# VoltageRegulator3_3V.net
KiCad netlist of a schematic drawn in Altium Designer
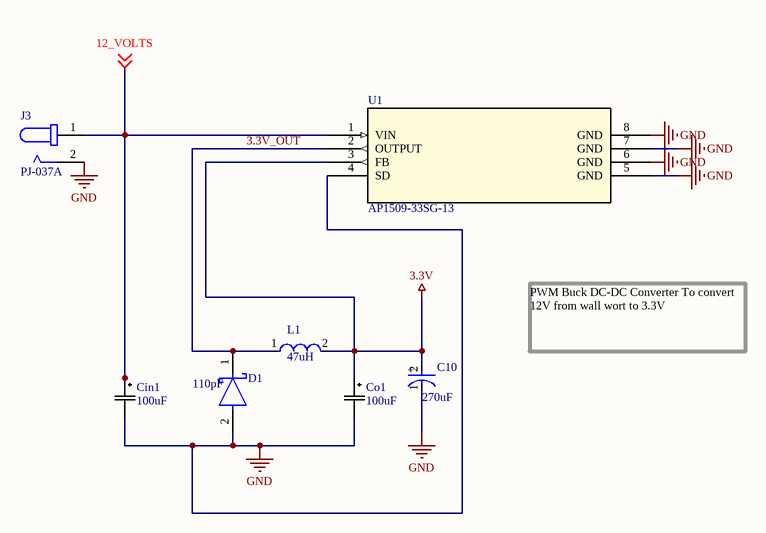
[diagram p0: VoltageRegulator3.3V.SchDoc]

(export (version "E")
  (design (tool "Eeschema 10.0.6"))
  (components
    (comp (ref "C10")
      (value "16SVPF270M")
      (footprint "FP-OS-CON-SMT-E7-MFG")
      (description "Conductive Polymer Aluminum Solid Capacitors (OS-CON) 270uF ±20% 16V RADIAL SMT 8x6.9mm")
      (fields
        (field (name "VOLTAGE") "16V")
        (field (name "CAPACITANCE") "270uF")
        (field (name "TOLERANCE") "20%")
      )
      (libsource (lib "Altium Content Vault") (part "cf48714ba7e38822c1575c7ec0b6d1f"))
    )
    (comp (ref "Cin1")
      (value "PCV1D101MCL2GS")
      (footprint "CAP_PC_8X7_NCH")
      (description "Cap Aluminum Polymer 100uF 20VDC 20% (8 X 7mm) SMD 0.042 Ohm 1400mA 3000h 105C Automotive T/R")
      (fields
        (field (name "MANUFACTURER") "Nichicon")
        (field (name "CAPACITANCE") "100uF")
        (field (name "TOLERANCE") "20%")
        (field (name "COPYRIGHT") "Copyright (C) 2022 Ultra Librarian. All rights reserved.")
      )
      (libsource (lib "PCV1D101MCL2GS") (part "PCV1D101MCL2GS"))
    )
    (comp (ref "Co1")
      (value "PCV1D101MCL2GS")
      (footprint "CAP_PC_8X7_NCH")
      (description "Cap Aluminum Polymer 100uF 20VDC 20% (8 X 7mm) SMD 0.042 Ohm 1400mA 3000h 105C Automotive T/R")
      (fields
        (field (name "MANUFACTURER") "Nichicon")
        (field (name "CAPACITANCE") "100uF")
        (field (name "TOLERANCE") "20%")
        (field (name "COPYRIGHT") "Copyright (C) 2022 Ultra Librarian. All rights reserved.")
      )
      (libsource (lib "PCV1D101MCL2GS") (part "PCV1D101MCL2GS"))
    )
    (comp (ref "D1")
      (value "B140-13-F")
      (footprint "FP-SMA-MFG")
      (description "DIODE SCHOTTKY 40V 1A SMA")
      (fields (field (name "CAPACITANCE") "110pF"))
      (libsource (lib "Altium Content Vault") (part "1d6ec82d83fb6aee721767c19dac4b9"))
    )
    (comp (ref "J3")
      (value "PJ-037A")
      (footprint "CUI_PJ-037A")
      (description "2.0 mm Center Pin, 2.5 A, Right Angle, Through Hole, Dc Power Jack Connector")
      (libsource (lib "PJ-037A") (part "PJ-037A"))
    )
    (comp (ref "L1")
      (value "47uH")
      (footprint "FP-LQM21DH_70-IPC_A")
      (description "Multilayer Type Inductor for Automotive, 0805 (2012), 47μH, 20%, 2.99Ω, 200mA")
      (fields
        (field (name "MANUFACTURER") "Murata")
        (field (name "MANUFACTURER PART NUMBER") "LQM21DH470M70L")
      )
      (libsource (lib "Altium Content Vault") (part "725321dda6339637d4d059423bc1c3c"))
    )
    (comp (ref "U1")
      (value "AP1509-33SG-13")
      (footprint "SOP-8L_DIO")
      (description "No Description Available")
      (fields (field (name "COPYRIGHT") "Copyright (C) 2022 Ultra Librarian. All rights reserved."))
      (libsource (lib "AP1509-33SG-13") (part "AP1509-33SG-13"))
    )
  )
  (nets
    (net (code "1") (name "/3.3V_OUT") (class "Default")
      (node (ref "D1") (pin "1") (pinfunction "C_1") (pintype "passive"))
      (node (ref "L1") (pin "1") (pinfunction "1_1") (pintype "passive"))
      (node (ref "U1") (pin "2") (pinfunction "OUTPUT_2") (pintype "output"))
    )
    (net (code "2") (name "3.3V") (class "Default")
      (node (ref "C10") (pin "2") (pinfunction "A_2") (pintype "passive"))
      (node (ref "Co1") (pin "1") (pinfunction "1_1") (pintype "passive"))
      (node (ref "L1") (pin "2") (pinfunction "2_2") (pintype "passive"))
      (node (ref "U1") (pin "3") (pinfunction "FB_3") (pintype "output"))
    )
    (net (code "3") (name "12_VOLTS") (class "Default")
      (node (ref "Cin1") (pin "1") (pinfunction "1_1") (pintype "passive"))
      (node (ref "J3") (pin "1") (pinfunction "1_1") (pintype "passive"))
      (node (ref "U1") (pin "1") (pinfunction "VIN_1") (pintype "input"))
    )
    (net (code "4") (name "GND") (class "Default")
      (node (ref "C10") (pin "1") (pinfunction "C_1") (pintype "passive"))
      (node (ref "Cin1") (pin "2") (pinfunction "2_2") (pintype "passive"))
      (node (ref "Co1") (pin "2") (pinfunction "2_2") (pintype "passive"))
      (node (ref "D1") (pin "2") (pinfunction "A_2") (pintype "passive"))
      (node (ref "J3") (pin "2") (pinfunction "2_2") (pintype "passive"))
      (node (ref "U1") (pin "4") (pinfunction "SD_4") (pintype "passive"))
      (node (ref "U1") (pin "5") (pinfunction "GND_5") (pintype "power_in"))
      (node (ref "U1") (pin "6") (pinfunction "GND_6") (pintype "power_in"))
      (node (ref "U1") (pin "7") (pinfunction "GND_7") (pintype "power_in"))
      (node (ref "U1") (pin "8") (pinfunction "GND_8") (pintype "power_in"))
    )
  )
)
